# v2-landshark-handheld-controller.net
KiCad netlist of a schematic drawn in EAGLE
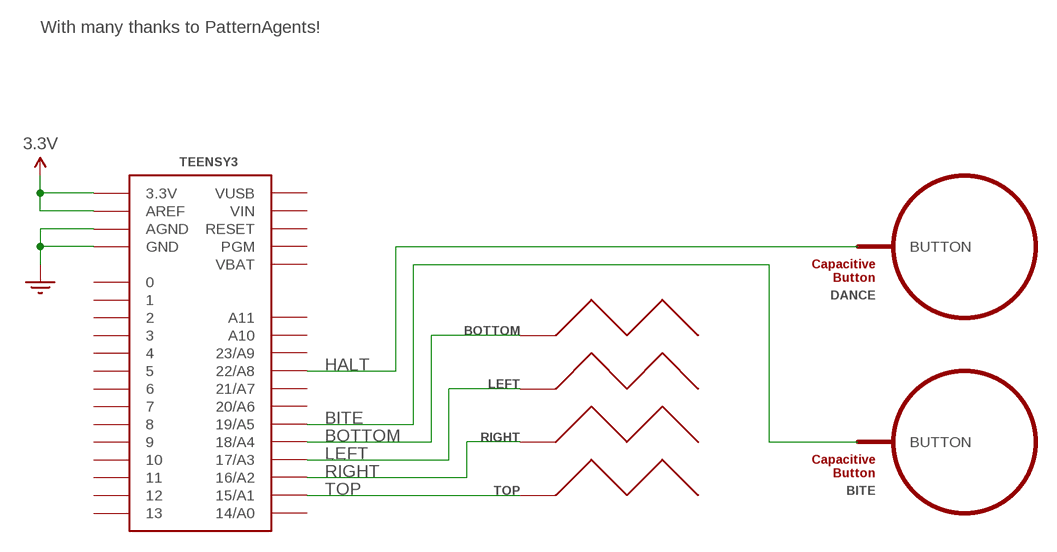
[diagram p0: schematic, sheet 1]

(export (version "E")
  (design (tool "Eeschema 10.0.6"))
  (components
    (comp (ref "BITE")
      (value "BUTTON_PASSIVE12MM")
      (footprint "eagle-import:BUTTON_PASSIVE_12MM")
      (libsource (lib "eagle-import") (part "BUTTON_PASSIVE12MM"))
    )
    (comp (ref "BOTTOM")
      (value "SLIDER_PASSIVE_1SEG")
      (footprint "eagle-import:SLIDER_PASSIVE_1SEG_12MM")
      (libsource (lib "eagle-import") (part "SLIDER_PASSIVE_1SEG"))
    )
    (comp (ref "DANCE")
      (value "BUTTON_PASSIVE12MM")
      (footprint "eagle-import:BUTTON_PASSIVE_12MM")
      (libsource (lib "eagle-import") (part "BUTTON_PASSIVE12MM"))
    )
    (comp (ref "LEFT")
      (value "SLIDER_PASSIVE_1SEG")
      (footprint "eagle-import:SLIDER_PASSIVE_1SEG_12MM")
      (libsource (lib "eagle-import") (part "SLIDER_PASSIVE_1SEG"))
    )
    (comp (ref "RIGHT")
      (value "SLIDER_PASSIVE_1SEG")
      (footprint "eagle-import:SLIDER_PASSIVE_1SEG_12MM")
      (libsource (lib "eagle-import") (part "SLIDER_PASSIVE_1SEG"))
    )
    (comp (ref "TEENSY3")
      (value "TEENSY_3.0+4")
      (footprint "eagle-import:TEENSY_3.0+4")
      (libsource (lib "eagle-import") (part "TEENSY_3.0+4"))
    )
    (comp (ref "TOP")
      (value "SLIDER_PASSIVE_1SEG")
      (footprint "eagle-import:SLIDER_PASSIVE_1SEG_12MM")
      (libsource (lib "eagle-import") (part "SLIDER_PASSIVE_1SEG"))
    )
  )
  (nets
    (net (code "1") (name "/BITE") (class "Default")
      (node (ref "BITE") (pin "BUTTON") (pinfunction "BUTTON_BUTTON") (pintype "passive"))
      (node (ref "TEENSY3") (pin "19/A5") (pinfunction "19/A5_19/A5") (pintype "bidirectional"))
    )
    (net (code "2") (name "/BOTTOM") (class "Default")
      (node (ref "BOTTOM") (pin "P$1") (pinfunction "SL1_P$1") (pintype "passive"))
      (node (ref "TEENSY3") (pin "18/A4") (pinfunction "18/A4_18/A4") (pintype "bidirectional"))
    )
    (net (code "3") (name "/HALT") (class "Default")
      (node (ref "DANCE") (pin "BUTTON") (pinfunction "BUTTON_BUTTON") (pintype "passive"))
      (node (ref "TEENSY3") (pin "22/A8") (pinfunction "22/A8_22/A8") (pintype "bidirectional"))
    )
    (net (code "4") (name "/LEFT") (class "Default")
      (node (ref "LEFT") (pin "P$1") (pinfunction "SL1_P$1") (pintype "passive"))
      (node (ref "TEENSY3") (pin "17/A3") (pinfunction "17/A3_17/A3") (pintype "bidirectional"))
    )
    (net (code "5") (name "/RIGHT") (class "Default")
      (node (ref "RIGHT") (pin "P$1") (pinfunction "SL1_P$1") (pintype "passive"))
      (node (ref "TEENSY3") (pin "16/A2") (pinfunction "16/A2_16/A2") (pintype "bidirectional"))
    )
    (net (code "6") (name "/TOP") (class "Default")
      (node (ref "TEENSY3") (pin "15/A1") (pinfunction "15/A1_15/A1") (pintype "bidirectional"))
      (node (ref "TOP") (pin "P$1") (pinfunction "SL1_P$1") (pintype "passive"))
    )
    (net (code "7") (name "/VBAT") (class "Default")
      (node (ref "TEENSY3") (pin "VBAT") (pinfunction "VBAT_VBAT") (pintype "power_in"))
    )
    (net (code "8") (name "/VIN") (class "Default")
      (node (ref "TEENSY3") (pin "VIN") (pinfunction "VIN_VIN") (pintype "power_in"))
    )
    (net (code "9") (name "/VUSB") (class "Default")
      (node (ref "TEENSY3") (pin "VUSB") (pinfunction "VUSB_VUSB") (pintype "power_in"))
    )
    (net (code "10") (name "3.3V") (class "Default")
      (node (ref "TEENSY3") (pin "3.3V") (pinfunction "3.3V_3.3V") (pintype "power_in"))
      (node (ref "TEENSY3") (pin "3.3V1") (pinfunction "3.3V_3.3V1") (pintype "power_in"))
      (node (ref "TEENSY3") (pin "AREF") (pinfunction "AREF_AREF") (pintype "power_in"))
    )
    (net (code "11") (name "GND") (class "Default")
      (node (ref "TEENSY3") (pin "AGND") (pinfunction "AGND_AGND") (pintype "power_in"))
      (node (ref "TEENSY3") (pin "GND") (pinfunction "GND_GND") (pintype "power_in"))
      (node (ref "TEENSY3") (pin "GND1") (pinfunction "GND_GND1") (pintype "power_in"))
    )
    (net (code "12") (name "unconnected-(TEENSY3-Pad0)") (class "Default")
      (node (ref "TEENSY3") (pin "0") (pinfunction "0_0") (pintype "bidirectional"))
    )
    (net (code "13") (name "unconnected-(TEENSY3-Pad1)") (class "Default")
      (node (ref "TEENSY3") (pin "1") (pinfunction "1_1") (pintype "bidirectional"))
    )
    (net (code "14") (name "unconnected-(TEENSY3-Pad2)") (class "Default")
      (node (ref "TEENSY3") (pin "2") (pinfunction "2_2") (pintype "bidirectional"))
    )
    (net (code "15") (name "unconnected-(TEENSY3-Pad3)") (class "Default")
      (node (ref "TEENSY3") (pin "3") (pinfunction "3_3") (pintype "bidirectional"))
    )
    (net (code "16") (name "unconnected-(TEENSY3-Pad4)") (class "Default")
      (node (ref "TEENSY3") (pin "4") (pinfunction "4_4") (pintype "bidirectional"))
    )
    (net (code "17") (name "unconnected-(TEENSY3-Pad5)") (class "Default")
      (node (ref "TEENSY3") (pin "5") (pinfunction "5_5") (pintype "bidirectional"))
    )
    (net (code "18") (name "unconnected-(TEENSY3-Pad6)") (class "Default")
      (node (ref "TEENSY3") (pin "6") (pinfunction "6_6") (pintype "bidirectional"))
    )
    (net (code "19") (name "unconnected-(TEENSY3-Pad7)") (class "Default")
      (node (ref "TEENSY3") (pin "7") (pinfunction "7_7") (pintype "bidirectional"))
    )
    (net (code "20") (name "unconnected-(TEENSY3-Pad8)") (class "Default")
      (node (ref "TEENSY3") (pin "8") (pinfunction "8_8") (pintype "bidirectional"))
    )
    (net (code "21") (name "unconnected-(TEENSY3-Pad9)") (class "Default")
      (node (ref "TEENSY3") (pin "9") (pinfunction "9_9") (pintype "bidirectional"))
    )
    (net (code "22") (name "unconnected-(TEENSY3-Pad10)") (class "Default")
      (node (ref "TEENSY3") (pin "10") (pinfunction "10_10") (pintype "bidirectional"))
    )
    (net (code "23") (name "unconnected-(TEENSY3-Pad11)") (class "Default")
      (node (ref "TEENSY3") (pin "11") (pinfunction "11_11") (pintype "bidirectional"))
    )
    (net (code "24") (name "unconnected-(TEENSY3-Pad12)") (class "Default")
      (node (ref "TEENSY3") (pin "12") (pinfunction "12_12") (pintype "bidirectional"))
    )
    (net (code "25") (name "unconnected-(TEENSY3-Pad13)") (class "Default")
      (node (ref "TEENSY3") (pin "13") (pinfunction "13_13") (pintype "bidirectional"))
    )
    (net (code "26") (name "unconnected-(TEENSY3-Pad14{slash}A0)") (class "Default")
      (node (ref "TEENSY3") (pin "14/A0") (pinfunction "14/A0_14/A0") (pintype "bidirectional"))
    )
    (net (code "27") (name "unconnected-(TEENSY3-Pad20{slash}A6)") (class "Default")
      (node (ref "TEENSY3") (pin "20/A6") (pinfunction "20/A6_20/A6") (pintype "bidirectional"))
    )
    (net (code "28") (name "unconnected-(TEENSY3-Pad21{slash}A7)") (class "Default")
      (node (ref "TEENSY3") (pin "21/A7") (pinfunction "21/A7_21/A7") (pintype "bidirectional"))
    )
    (net (code "29") (name "unconnected-(TEENSY3-Pad23{slash}A9)") (class "Default")
      (node (ref "TEENSY3") (pin "23/A9") (pinfunction "23/A9_23/A9") (pintype "bidirectional"))
    )
    (net (code "30") (name "unconnected-(TEENSY3-PadA10)") (class "Default")
      (node (ref "TEENSY3") (pin "A10") (pinfunction "A10_A10") (pintype "bidirectional"))
    )
    (net (code "31") (name "unconnected-(TEENSY3-PadA11)") (class "Default")
      (node (ref "TEENSY3") (pin "A11") (pinfunction "A11_A11") (pintype "bidirectional"))
    )
    (net (code "32") (name "unconnected-(TEENSY3-PadPGM)") (class "Default")
      (node (ref "TEENSY3") (pin "PGM") (pinfunction "PGM_PGM") (pintype "bidirectional"))
    )
    (net (code "33") (name "unconnected-(TEENSY3-PadRESET)") (class "Default")
      (node (ref "TEENSY3") (pin "RESET") (pinfunction "RESET_RESET") (pintype "bidirectional"))
    )
  )
)
